# raspberry_pi.net
KiCad netlist of a schematic drawn in Altium Designer
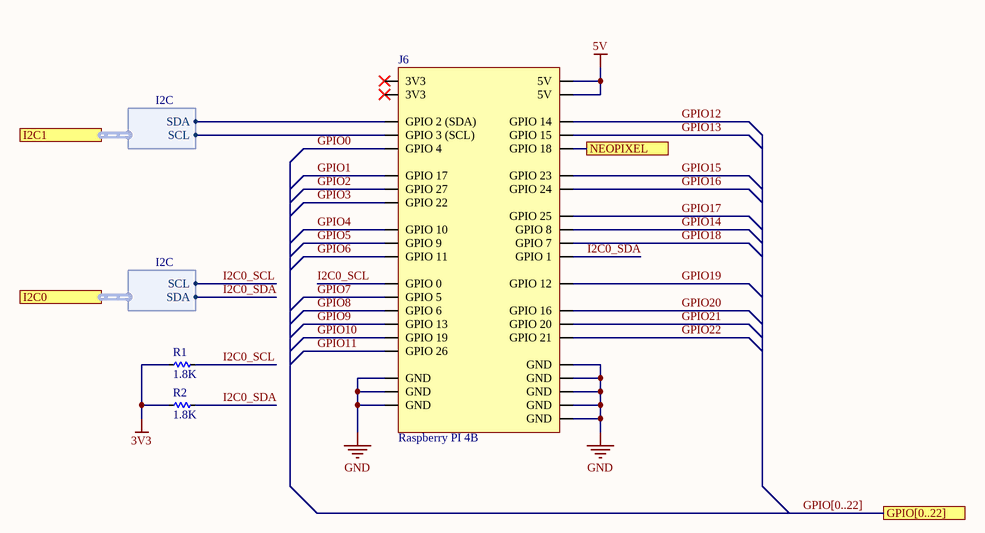
[diagram p0: raspberry_pi.SchDoc]

(export (version "E")
  (design (tool "Eeschema 10.0.6"))
  (components
    (comp (ref "J6")
      (value "Raspberry PI 4B")
      (footprint "Raspberry PI 4B")
      (libsource (lib "brew_lib") (part "Raspberry PI 4B"))
    )
    (comp (ref "R1")
      (value "1.8K")
      (footprint "R1206")
      (description "Resistor, 1.80K Ohms, 1206, 0.25W, ±1%")
      (fields (field (name "MFG") "YAGEO") (field (name "POWER") "1/4W"))
      (libsource (lib "AltiumReleaseLibDB") (part "__Template_Resistor"))
    )
    (comp (ref "R2")
      (value "1.8K")
      (footprint "R1206")
      (description "Resistor, 1.80K Ohms, 1206, 0.25W, ±1%")
      (fields (field (name "MFG") "YAGEO") (field (name "POWER") "1/4W"))
      (libsource (lib "AltiumReleaseLibDB") (part "__Template_Resistor"))
    )
  )
  (nets
    (net (code "2") (name "/GPIO0") (class "Default")
      (node (ref "J6") (pin "7") (pinfunction "GPIO_4_7") (pintype "passive"))
    )
    (net (code "3") (name "/GPIO1") (class "Default")
      (node (ref "J6") (pin "11") (pinfunction "GPIO_17_11") (pintype "passive"))
    )
    (net (code "4") (name "/GPIO2") (class "Default")
      (node (ref "J6") (pin "13") (pinfunction "GPIO_27_13") (pintype "passive"))
    )
    (net (code "5") (name "/GPIO3") (class "Default")
      (node (ref "J6") (pin "15") (pinfunction "GPIO_22_15") (pintype "passive"))
    )
    (net (code "6") (name "/GPIO4") (class "Default")
      (node (ref "J6") (pin "19") (pinfunction "GPIO_10_19") (pintype "passive"))
    )
    (net (code "7") (name "/GPIO5") (class "Default")
      (node (ref "J6") (pin "21") (pinfunction "GPIO_9_21") (pintype "passive"))
    )
    (net (code "8") (name "/GPIO6") (class "Default")
      (node (ref "J6") (pin "23") (pinfunction "GPIO_11_23") (pintype "passive"))
    )
    (net (code "9") (name "/GPIO7") (class "Default")
      (node (ref "J6") (pin "29") (pinfunction "GPIO_5_29") (pintype "passive"))
    )
    (net (code "10") (name "/GPIO8") (class "Default")
      (node (ref "J6") (pin "31") (pinfunction "GPIO_6_31") (pintype "passive"))
    )
    (net (code "11") (name "/GPIO9") (class "Default")
      (node (ref "J6") (pin "33") (pinfunction "GPIO_13_33") (pintype "passive"))
    )
    (net (code "12") (name "/GPIO10") (class "Default")
      (node (ref "J6") (pin "35") (pinfunction "GPIO_19_35") (pintype "passive"))
    )
    (net (code "13") (name "/GPIO11") (class "Default")
      (node (ref "J6") (pin "37") (pinfunction "GPIO_26_37") (pintype "passive"))
    )
    (net (code "14") (name "/GPIO12") (class "Default")
      (node (ref "J6") (pin "8") (pinfunction "GPIO_14_8") (pintype "passive"))
    )
    (net (code "15") (name "/GPIO13") (class "Default")
      (node (ref "J6") (pin "10") (pinfunction "GPIO_15_10") (pintype "passive"))
    )
    (net (code "16") (name "/GPIO14") (class "Default")
      (node (ref "J6") (pin "24") (pinfunction "GPIO_8_24") (pintype "passive"))
    )
    (net (code "17") (name "/GPIO15") (class "Default")
      (node (ref "J6") (pin "16") (pinfunction "GPIO_23_16") (pintype "passive"))
    )
    (net (code "18") (name "/GPIO16") (class "Default")
      (node (ref "J6") (pin "18") (pinfunction "GPIO_24_18") (pintype "passive"))
    )
    (net (code "19") (name "/GPIO17") (class "Default")
      (node (ref "J6") (pin "22") (pinfunction "GPIO_25_22") (pintype "passive"))
    )
    (net (code "20") (name "/GPIO18") (class "Default")
      (node (ref "J6") (pin "26") (pinfunction "GPIO_7_26") (pintype "passive"))
    )
    (net (code "21") (name "/GPIO19") (class "Default")
      (node (ref "J6") (pin "32") (pinfunction "GPIO_12_32") (pintype "passive"))
    )
    (net (code "22") (name "/GPIO20") (class "Default")
      (node (ref "J6") (pin "36") (pinfunction "GPIO_16_36") (pintype "passive"))
    )
    (net (code "23") (name "/GPIO21") (class "Default")
      (node (ref "J6") (pin "38") (pinfunction "GPIO_20_38") (pintype "passive"))
    )
    (net (code "24") (name "/GPIO22") (class "Default")
      (node (ref "J6") (pin "40") (pinfunction "GPIO_21_40") (pintype "passive"))
    )
    (net (code "26") (name "/I2C0_SCL") (class "Default")
      (node (ref "J6") (pin "27") (pinfunction "GPIO_0_27") (pintype "passive"))
      (node (ref "R1") (pin "2") (pintype "passive"))
    )
    (net (code "27") (name "/I2C0_SDA") (class "Default")
      (node (ref "J6") (pin "28") (pinfunction "GPIO_1_28") (pintype "passive"))
      (node (ref "R2") (pin "2") (pintype "passive"))
    )
    (net (code "28") (name "/NEOPIXEL") (class "Default")
      (node (ref "J6") (pin "12") (pinfunction "GPIO_18_12") (pintype "passive"))
    )
    (net (code "30") (name "3V3") (class "Default")
      (node (ref "R1") (pin "1") (pintype "passive"))
      (node (ref "R2") (pin "1") (pintype "passive"))
    )
    (net (code "31") (name "5V") (class "Default")
      (node (ref "J6") (pin "2") (pinfunction "5V_2") (pintype "passive"))
      (node (ref "J6") (pin "4") (pinfunction "5V_4") (pintype "passive"))
    )
    (net (code "32") (name "GND") (class "Default")
      (node (ref "J6") (pin "14") (pinfunction "GND_14") (pintype "passive"))
      (node (ref "J6") (pin "20") (pinfunction "GND_20") (pintype "passive"))
      (node (ref "J6") (pin "25") (pinfunction "GND_25") (pintype "passive"))
      (node (ref "J6") (pin "30") (pinfunction "GND_30") (pintype "passive"))
      (node (ref "J6") (pin "34") (pinfunction "GND_34") (pintype "passive"))
      (node (ref "J6") (pin "39") (pinfunction "GND_39") (pintype "passive"))
      (node (ref "J6") (pin "6") (pinfunction "GND_6") (pintype "passive"))
      (node (ref "J6") (pin "9") (pinfunction "GND_9") (pintype "passive"))
    )
    (net (code "33") (name "unconnected-(J6-3V3-Pad1)") (class "Default")
      (node (ref "J6") (pin "1") (pinfunction "3V3_1") (pintype "passive+no_connect"))
    )
    (net (code "34") (name "unconnected-(J6-3V3-Pad17)") (class "Default")
      (node (ref "J6") (pin "17") (pinfunction "3V3_17") (pintype "passive+no_connect"))
    )
    (net (code "35") (name "unconnected-(J6-GPIO_2_(SDA)-Pad3)") (class "Default")
      (node (ref "J6") (pin "3") (pinfunction "GPIO_2_(SDA)_3") (pintype "passive"))
    )
    (net (code "36") (name "unconnected-(J6-GPIO_3_(SCL)-Pad5)") (class "Default")
      (node (ref "J6") (pin "5") (pinfunction "GPIO_3_(SCL)_5") (pintype "passive"))
    )
  )
)
